# ProPrj_4s2p_18650_holder_2025-11-21.net
KiCad netlist of a schematic drawn in EasyEDA Pro
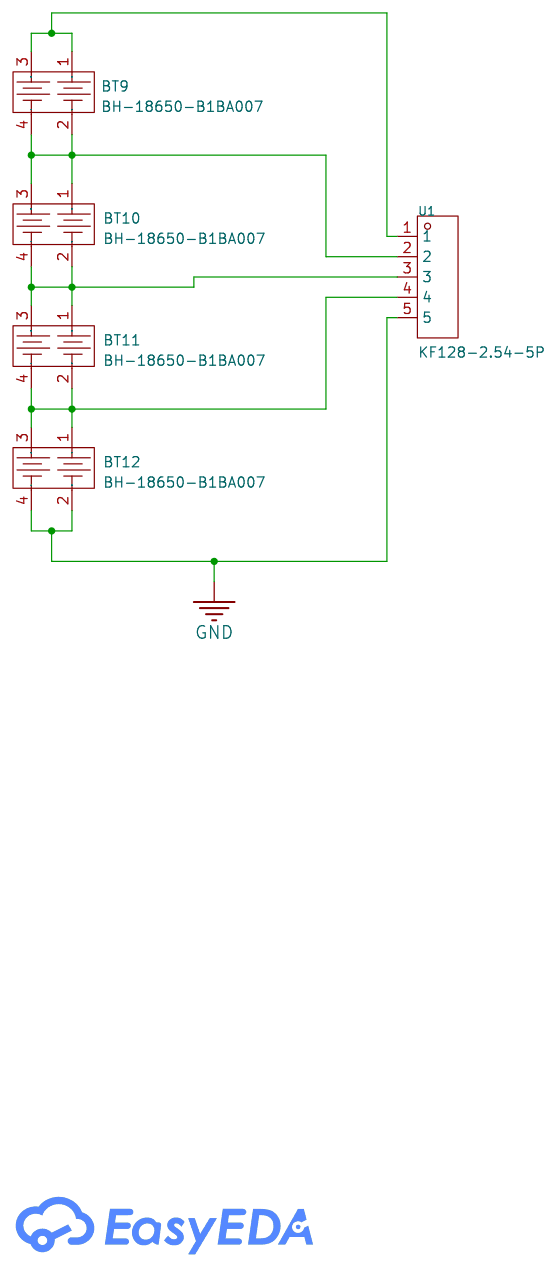
[diagram p0: schematic sheet]

(export (version "E")
  (design (tool "Eeschema 10.0.6"))
  (components
    (comp (ref "BT9")
      (value "BH-18650-B1BA007")
      (footprint "easyedapro:BAT-SMD_BH-18650-B1BA007")
      (fields (field (name "Manufacturer") "MYOUNG(美阳)"))
      (libsource (lib "easyedapro") (part "BH-18650-B1BA007"))
    )
    (comp (ref "BT10")
      (value "BH-18650-B1BA007")
      (footprint "easyedapro:BAT-SMD_BH-18650-B1BA007")
      (fields (field (name "Manufacturer") "MYOUNG(美阳)"))
      (libsource (lib "easyedapro") (part "BH-18650-B1BA007"))
    )
    (comp (ref "BT11")
      (value "BH-18650-B1BA007")
      (footprint "easyedapro:BAT-SMD_BH-18650-B1BA007")
      (fields (field (name "Manufacturer") "MYOUNG(美阳)"))
      (libsource (lib "easyedapro") (part "BH-18650-B1BA007"))
    )
    (comp (ref "BT12")
      (value "BH-18650-B1BA007")
      (footprint "easyedapro:BAT-SMD_BH-18650-B1BA007")
      (fields (field (name "Manufacturer") "MYOUNG(美阳)"))
      (libsource (lib "easyedapro") (part "BH-18650-B1BA007"))
    )
    (comp (ref "U1")
      (value "KF128-2.54-5P")
      (footprint "easyedapro:CONN-TH_5P-P2.54_KF128-2.54-5P")
      (fields (field (name "Manufacturer") "KEFA(科发)"))
      (libsource (lib "easyedapro") (part "KF128-2.54-5P"))
    )
  )
  (nets
    (net (code "1") (name "GND") (class "Default")
      (node (ref "BT12") (pin "2") (pinfunction "2_2") (pintype "input"))
      (node (ref "BT12") (pin "4") (pinfunction "4_4") (pintype "input"))
      (node (ref "U1") (pin "5") (pinfunction "5_5") (pintype "input"))
    )
    (net (code "2") (name "Net-(BT9-Pad1)") (class "Default")
      (node (ref "BT9") (pin "1") (pinfunction "1_1") (pintype "input"))
      (node (ref "BT9") (pin "3") (pinfunction "3_3") (pintype "input"))
      (node (ref "U1") (pin "1") (pinfunction "1_1") (pintype "input"))
    )
    (net (code "3") (name "Net-(BT10-Pad1)") (class "Default")
      (node (ref "BT10") (pin "1") (pinfunction "1_1") (pintype "input"))
      (node (ref "BT10") (pin "3") (pinfunction "3_3") (pintype "input"))
      (node (ref "BT9") (pin "2") (pinfunction "2_2") (pintype "input"))
      (node (ref "BT9") (pin "4") (pinfunction "4_4") (pintype "input"))
      (node (ref "U1") (pin "2") (pinfunction "2_2") (pintype "input"))
    )
    (net (code "4") (name "Net-(BT10-Pad2)") (class "Default")
      (node (ref "BT10") (pin "2") (pinfunction "2_2") (pintype "input"))
      (node (ref "BT10") (pin "4") (pinfunction "4_4") (pintype "input"))
      (node (ref "BT11") (pin "1") (pinfunction "1_1") (pintype "input"))
      (node (ref "BT11") (pin "3") (pinfunction "3_3") (pintype "input"))
      (node (ref "U1") (pin "3") (pinfunction "3_3") (pintype "input"))
    )
    (net (code "5") (name "Net-(BT11-Pad2)") (class "Default")
      (node (ref "BT11") (pin "2") (pinfunction "2_2") (pintype "input"))
      (node (ref "BT11") (pin "4") (pinfunction "4_4") (pintype "input"))
      (node (ref "BT12") (pin "1") (pinfunction "1_1") (pintype "input"))
      (node (ref "BT12") (pin "3") (pinfunction "3_3") (pintype "input"))
      (node (ref "U1") (pin "4") (pinfunction "4_4") (pintype "input"))
    )
  )
)
